# MiniDMXSlave.net
KiCad netlist of a schematic drawn in EAGLE
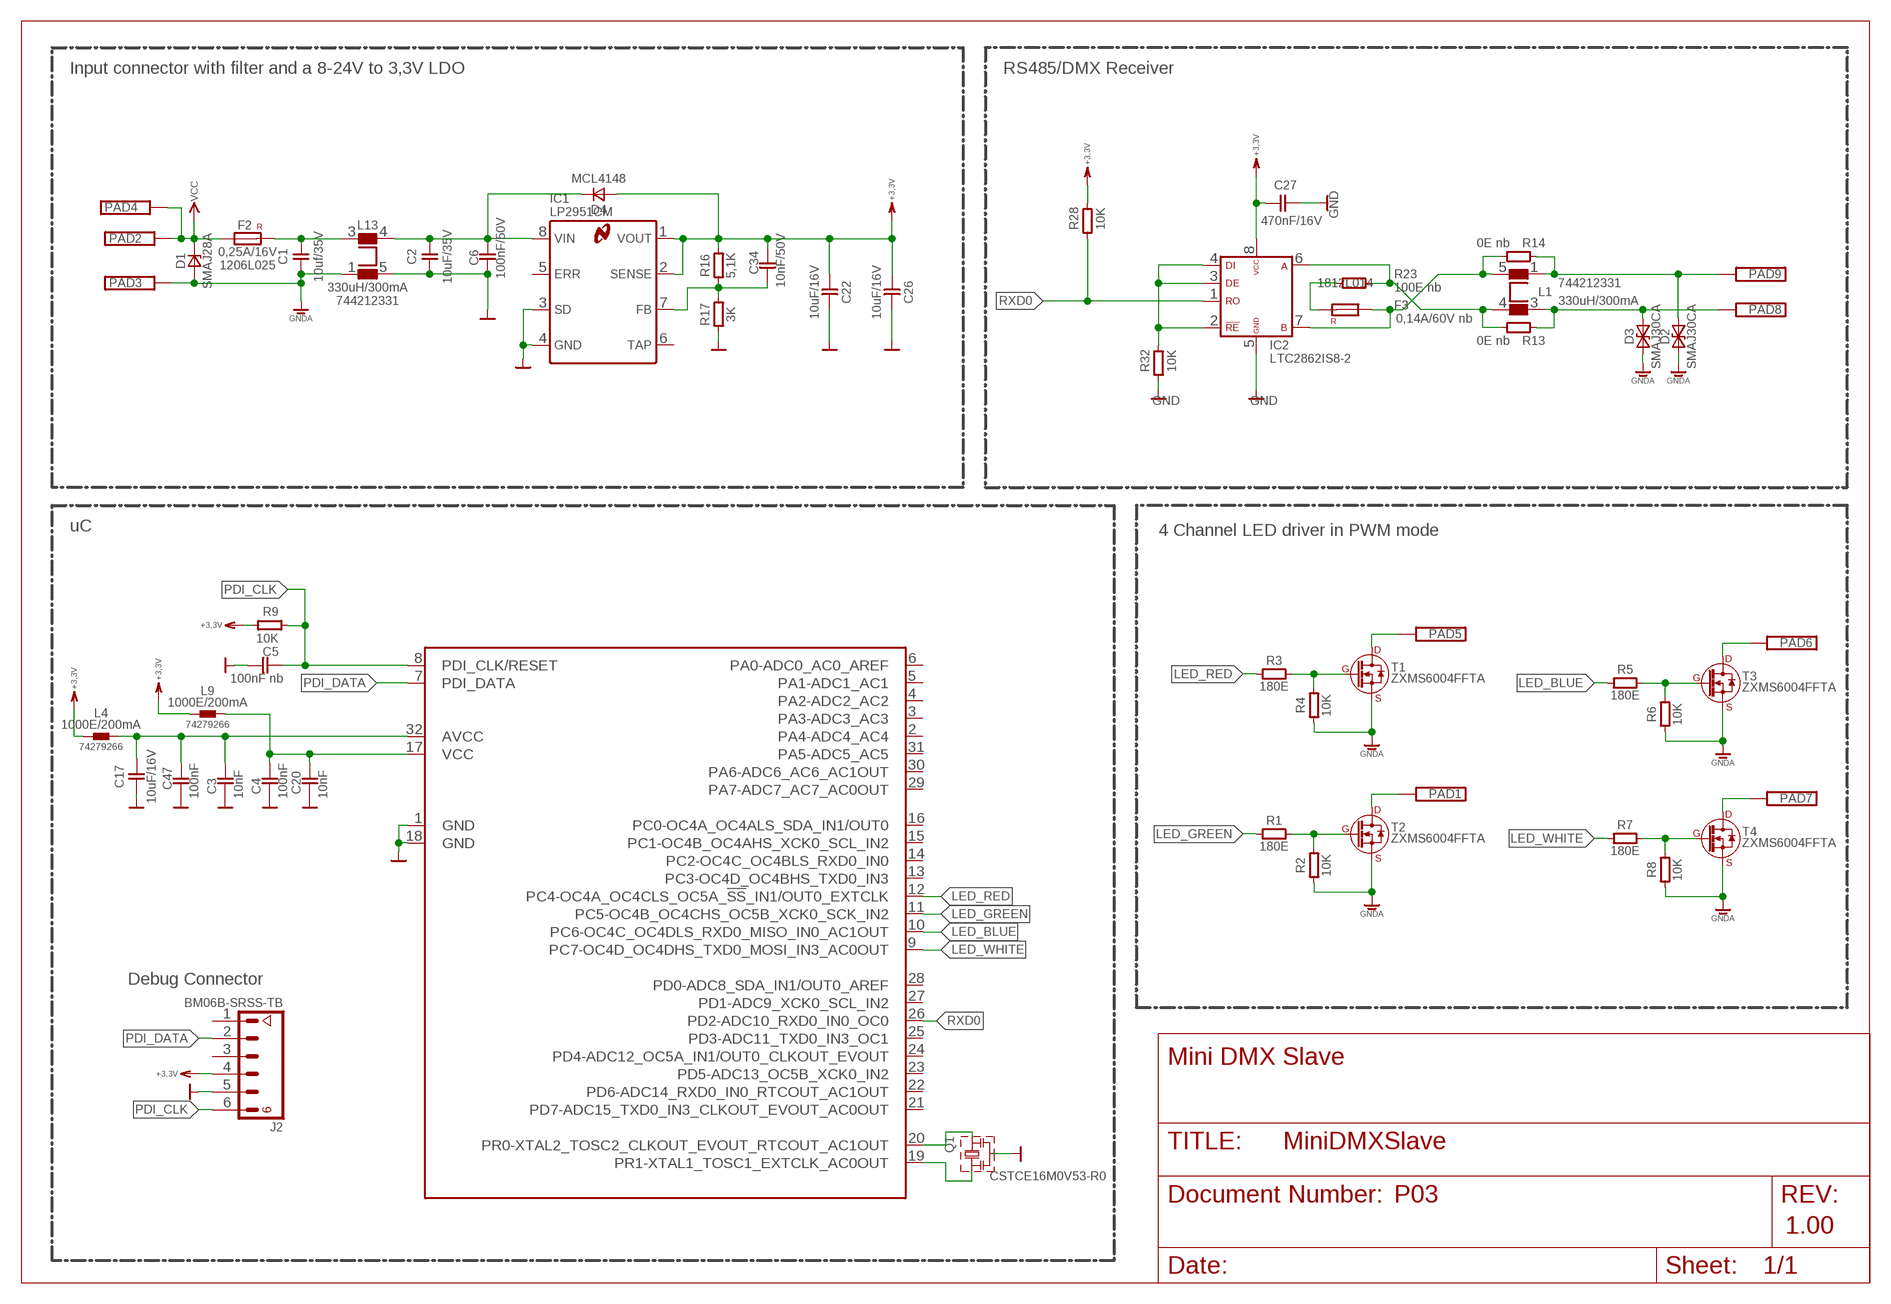
[diagram p0: schematic, sheet 1]

(export (version "E")
  (design (tool "Eeschema 10.0.6"))
  (components
    (comp (ref "C1")
      (value "10uf/35V")
      (footprint "eagle-import:1206")
      (libsource (lib "eagle-import") (part "C-1206"))
    )
    (comp (ref "C2")
      (value "10uF/35V")
      (footprint "eagle-import:1206")
      (libsource (lib "eagle-import") (part "C-1206"))
    )
    (comp (ref "C3")
      (value "10nF")
      (footprint "eagle-import:0603")
      (libsource (lib "eagle-import") (part "C-0603"))
    )
    (comp (ref "C4")
      (value "100nF")
      (footprint "eagle-import:0603")
      (libsource (lib "eagle-import") (part "C-0603"))
    )
    (comp (ref "C5")
      (value "100nF nb")
      (footprint "eagle-import:0603")
      (libsource (lib "eagle-import") (part "C-0603"))
    )
    (comp (ref "C6")
      (value "100nF/50V")
      (footprint "eagle-import:0603")
      (libsource (lib "eagle-import") (part "C-0603"))
    )
    (comp (ref "C17")
      (value "10uF/16V")
      (footprint "eagle-import:0805")
      (libsource (lib "eagle-import") (part "C-0805"))
    )
    (comp (ref "C20")
      (value "10nF")
      (footprint "eagle-import:0603")
      (libsource (lib "eagle-import") (part "C-0603"))
    )
    (comp (ref "C22")
      (value "10uF/16V")
      (footprint "eagle-import:0805")
      (libsource (lib "eagle-import") (part "C-0805"))
    )
    (comp (ref "C26")
      (value "10uF/16V")
      (footprint "eagle-import:0805")
      (libsource (lib "eagle-import") (part "C-0805"))
    )
    (comp (ref "C27")
      (value "470nF/16V")
      (footprint "eagle-import:0603")
      (libsource (lib "eagle-import") (part "C-0603"))
    )
    (comp (ref "C34")
      (value "10nF/50V")
      (footprint "eagle-import:0603")
      (libsource (lib "eagle-import") (part "C-0603"))
    )
    (comp (ref "C47")
      (value "100nF")
      (footprint "eagle-import:0603")
      (libsource (lib "eagle-import") (part "C-0603"))
    )
    (comp (ref "D1")
      (value "SMAJ28A")
      (footprint "eagle-import:DO-214AC")
      (libsource (lib "eagle-import") (part "SMAJA28"))
    )
    (comp (ref "D2")
      (value "SMAJ30CA")
      (footprint "eagle-import:DO-214AC")
      (libsource (lib "eagle-import") (part "SMAJCA30"))
    )
    (comp (ref "D3")
      (value "SMAJ30CA")
      (footprint "eagle-import:DO-214AC")
      (libsource (lib "eagle-import") (part "SMAJCA30"))
    )
    (comp (ref "D4")
      (value "MCL4148")
      (footprint "eagle-import:MICROMELF")
      (libsource (lib "eagle-import") (part "?4148MCL"))
    )
    (comp (ref "F2")
      (value "0,25A/16V")
      (footprint "eagle-import:1206L")
      (fields (field (name "MPN") "1206L025"))
      (libsource (lib "eagle-import") (part "1206L025"))
    )
    (comp (ref "F3")
      (value "0,14A/60V nb")
      (footprint "eagle-import:1812L")
      (fields (field (name "MPN") "1812L014"))
      (libsource (lib "eagle-import") (part "1812L014"))
    )
    (comp (ref "IC1")
      (value "LP2951CM")
      (footprint "eagle-import:SO8")
      (libsource (lib "eagle-import") (part "LP2951CM"))
    )
    (comp (ref "IC2")
      (value "LTC2862IS8-2")
      (footprint "eagle-import:SO8")
      (fields (field (name "MPN") "LTC2862IS8-2#TRPBF"))
      (libsource (lib "eagle-import") (part "LTC2862?-2S8I"))
    )
    (comp (ref "IC3")
      (value "E5-TQFP")
      (footprint "eagle-import:TQFP32")
      (libsource (lib "eagle-import") (part "E5-TQFP"))
    )
    (comp (ref "J2")
      (value "BM06B-SRSS-TB")
      (footprint "eagle-import:BM06B-SRSS-TB")
      (libsource (lib "eagle-import") (part "?M06B-SRSS-TBB"))
    )
    (comp (ref "L1")
      (value "330uH/300mA")
      (footprint "eagle-import:WE-SL1")
      (fields (field (name "MPN") "744212331"))
      (libsource (lib "eagle-import") (part "WE-SL1-330UH/300MA"))
    )
    (comp (ref "L4")
      (value "1000E/200mA")
      (footprint "eagle-import:0603")
      (fields (field (name "MPN") "74279266"))
      (libsource (lib "eagle-import") (part "WE-CBF-0603-1000E/200MA"))
    )
    (comp (ref "L9")
      (value "1000E/200mA")
      (footprint "eagle-import:0603")
      (fields (field (name "MPN") "74279266"))
      (libsource (lib "eagle-import") (part "WE-CBF-0603-1000E/200MA"))
    )
    (comp (ref "L13")
      (value "330uH/300mA")
      (footprint "eagle-import:WE-SL1")
      (fields (field (name "MPN") "744212331"))
      (libsource (lib "eagle-import") (part "WE-SL1-330UH/300MA"))
    )
    (comp (ref "PAD1")
      (value "PADS-6X3")
      (footprint "eagle-import:PAD_6MMX3MM")
      (libsource (lib "eagle-import") (part "PADS-6X3"))
    )
    (comp (ref "PAD2")
      (value "PADS-6X3")
      (footprint "eagle-import:PAD_6MMX3MM")
      (libsource (lib "eagle-import") (part "PADS-6X3"))
    )
    (comp (ref "PAD3")
      (value "PADS-6X3")
      (footprint "eagle-import:PAD_6MMX3MM")
      (libsource (lib "eagle-import") (part "PADS-6X3"))
    )
    (comp (ref "PAD4")
      (value "PADS-6X3")
      (footprint "eagle-import:PAD_6MMX3MM")
      (libsource (lib "eagle-import") (part "PADS-6X3"))
    )
    (comp (ref "PAD5")
      (value "PADS-6X3")
      (footprint "eagle-import:PAD_6MMX3MM")
      (libsource (lib "eagle-import") (part "PADS-6X3"))
    )
    (comp (ref "PAD6")
      (value "PADS-6X3")
      (footprint "eagle-import:PAD_6MMX3MM")
      (libsource (lib "eagle-import") (part "PADS-6X3"))
    )
    (comp (ref "PAD7")
      (value "PADS-6X3")
      (footprint "eagle-import:PAD_6MMX3MM")
      (libsource (lib "eagle-import") (part "PADS-6X3"))
    )
    (comp (ref "PAD8")
      (value "PADS-6X3")
      (footprint "eagle-import:PAD_6MMX3MM")
      (libsource (lib "eagle-import") (part "PADS-6X3"))
    )
    (comp (ref "PAD9")
      (value "PADS-6X3")
      (footprint "eagle-import:PAD_6MMX3MM")
      (libsource (lib "eagle-import") (part "PADS-6X3"))
    )
    (comp (ref "Q1")
      (value "CSTCE16M0V53-R0")
      (footprint "eagle-import:CSTCE_G_&_V")
      (libsource (lib "eagle-import") (part "CSTC?E_G_&_V"))
    )
    (comp (ref "R1")
      (value "180E")
      (footprint "eagle-import:0603")
      (libsource (lib "eagle-import") (part "R-0603"))
    )
    (comp (ref "R2")
      (value "10K")
      (footprint "eagle-import:0603")
      (libsource (lib "eagle-import") (part "R-0603"))
    )
    (comp (ref "R3")
      (value "180E")
      (footprint "eagle-import:0603")
      (libsource (lib "eagle-import") (part "R-0603"))
    )
    (comp (ref "R4")
      (value "10K")
      (footprint "eagle-import:0603")
      (libsource (lib "eagle-import") (part "R-0603"))
    )
    (comp (ref "R5")
      (value "180E")
      (footprint "eagle-import:0603")
      (libsource (lib "eagle-import") (part "R-0603"))
    )
    (comp (ref "R6")
      (value "10K")
      (footprint "eagle-import:0603")
      (libsource (lib "eagle-import") (part "R-0603"))
    )
    (comp (ref "R7")
      (value "180E")
      (footprint "eagle-import:0603")
      (libsource (lib "eagle-import") (part "R-0603"))
    )
    (comp (ref "R8")
      (value "10K")
      (footprint "eagle-import:0603")
      (libsource (lib "eagle-import") (part "R-0603"))
    )
    (comp (ref "R9")
      (value "10K")
      (footprint "eagle-import:0603")
      (libsource (lib "eagle-import") (part "R-0603"))
    )
    (comp (ref "R13")
      (value "0E nb")
      (footprint "eagle-import:0805")
      (libsource (lib "eagle-import") (part "R-0805"))
    )
    (comp (ref "R14")
      (value "0E nb")
      (footprint "eagle-import:0805")
      (libsource (lib "eagle-import") (part "R-0805"))
    )
    (comp (ref "R16")
      (value "5,1K")
      (footprint "eagle-import:0603")
      (libsource (lib "eagle-import") (part "R-0603"))
    )
    (comp (ref "R17")
      (value "3K")
      (footprint "eagle-import:0603")
      (libsource (lib "eagle-import") (part "R-0603"))
    )
    (comp (ref "R23")
      (value "100E nb")
      (footprint "eagle-import:0207")
      (libsource (lib "eagle-import") (part "R-0207"))
    )
    (comp (ref "R28")
      (value "10K")
      (footprint "eagle-import:0603")
      (libsource (lib "eagle-import") (part "R-0603"))
    )
    (comp (ref "R32")
      (value "10K")
      (footprint "eagle-import:0603")
      (libsource (lib "eagle-import") (part "R-0603"))
    )
    (comp (ref "T1")
      (value "ZXMS6004FFTA")
      (footprint "eagle-import:SOT-23")
      (libsource (lib "eagle-import") (part "ZXMS6004?TAFF"))
    )
    (comp (ref "T2")
      (value "ZXMS6004FFTA")
      (footprint "eagle-import:SOT-23")
      (libsource (lib "eagle-import") (part "ZXMS6004?TAFF"))
    )
    (comp (ref "T3")
      (value "ZXMS6004FFTA")
      (footprint "eagle-import:SOT-23")
      (libsource (lib "eagle-import") (part "ZXMS6004?TAFF"))
    )
    (comp (ref "T4")
      (value "ZXMS6004FFTA")
      (footprint "eagle-import:SOT-23")
      (libsource (lib "eagle-import") (part "ZXMS6004?TAFF"))
    )
  )
  (nets
    (net (code "1") (name "+3,3V") (class "Default")
      (node (ref "C22") (pin "1") (pinfunction "1_1") (pintype "passive"))
      (node (ref "C26") (pin "1") (pinfunction "1_1") (pintype "passive"))
      (node (ref "C27") (pin "2") (pinfunction "2_2") (pintype "passive"))
      (node (ref "C34") (pin "2") (pinfunction "2_2") (pintype "passive"))
      (node (ref "D4") (pin "A") (pinfunction "A_A") (pintype "passive"))
      (node (ref "IC1") (pin "1") (pinfunction "VOUT_1") (pintype "power_in"))
      (node (ref "IC1") (pin "2") (pinfunction "SENSE_2") (pintype "bidirectional"))
      (node (ref "IC2") (pin "8") (pinfunction "VCC_8") (pintype "power_in"))
      (node (ref "J2") (pin "4") (pinfunction "4_4") (pintype "passive"))
      (node (ref "L4") (pin "1") (pinfunction "1_1") (pintype "passive"))
      (node (ref "L9") (pin "1") (pinfunction "1_1") (pintype "passive"))
      (node (ref "R16") (pin "2") (pinfunction "2_2") (pintype "passive"))
      (node (ref "R28") (pin "2") (pinfunction "2_2") (pintype "passive"))
      (node (ref "R9") (pin "2") (pinfunction "2_2") (pintype "passive"))
    )
    (net (code "2") (name "GND") (class "Default")
      (node (ref "C17") (pin "1") (pinfunction "1_1") (pintype "passive"))
      (node (ref "C2") (pin "1") (pinfunction "1_1") (pintype "passive"))
      (node (ref "C20") (pin "1") (pinfunction "1_1") (pintype "passive"))
      (node (ref "C22") (pin "2") (pinfunction "2_2") (pintype "passive"))
      (node (ref "C26") (pin "2") (pinfunction "2_2") (pintype "passive"))
      (node (ref "C27") (pin "1") (pinfunction "1_1") (pintype "passive"))
      (node (ref "C3") (pin "1") (pinfunction "1_1") (pintype "passive"))
      (node (ref "C4") (pin "1") (pinfunction "1_1") (pintype "passive"))
      (node (ref "C47") (pin "1") (pinfunction "1_1") (pintype "passive"))
      (node (ref "C5") (pin "2") (pinfunction "2_2") (pintype "passive"))
      (node (ref "C6") (pin "1") (pinfunction "1_1") (pintype "passive"))
      (node (ref "IC1") (pin "3") (pinfunction "SD_3") (pintype "bidirectional"))
      (node (ref "IC1") (pin "4") (pinfunction "GND_4") (pintype "power_in"))
      (node (ref "IC2") (pin "5") (pinfunction "GND_5") (pintype "power_in"))
      (node (ref "IC3") (pin "1") (pinfunction "GND_1") (pintype "power_in"))
      (node (ref "IC3") (pin "18") (pinfunction "GND_18") (pintype "power_in"))
      (node (ref "J2") (pin "5") (pinfunction "5_5") (pintype "passive"))
      (node (ref "L13") (pin "5") (pinfunction "2_5") (pintype "passive"))
      (node (ref "Q1") (pin "2") (pinfunction "GND_2") (pintype "power_in"))
      (node (ref "R17") (pin "1") (pinfunction "1_1") (pintype "passive"))
      (node (ref "R32") (pin "1") (pinfunction "1_1") (pintype "passive"))
    )
    (net (code "3") (name "GNDA") (class "Default")
      (node (ref "C1") (pin "1") (pinfunction "1_1") (pintype "passive"))
      (node (ref "D1") (pin "A") (pinfunction "A_A") (pintype "passive"))
      (node (ref "D2") (pin "K") (pinfunction "2_K") (pintype "passive"))
      (node (ref "D3") (pin "K") (pinfunction "2_K") (pintype "passive"))
      (node (ref "L13") (pin "1") (pinfunction "1_1") (pintype "passive"))
      (node (ref "PAD3") (pin "1") (pinfunction "1_1") (pintype "bidirectional"))
      (node (ref "R2") (pin "1") (pinfunction "1_1") (pintype "passive"))
      (node (ref "R4") (pin "1") (pinfunction "1_1") (pintype "passive"))
      (node (ref "R6") (pin "1") (pinfunction "1_1") (pintype "passive"))
      (node (ref "R8") (pin "1") (pinfunction "1_1") (pintype "passive"))
      (node (ref "T1") (pin "2") (pinfunction "S_2") (pintype "passive"))
      (node (ref "T2") (pin "2") (pinfunction "S_2") (pintype "passive"))
      (node (ref "T3") (pin "2") (pinfunction "S_2") (pintype "passive"))
      (node (ref "T4") (pin "2") (pinfunction "S_2") (pintype "passive"))
    )
    (net (code "4") (name "LED_BLUE") (class "Default")
      (node (ref "IC3") (pin "10") (pinfunction "PC6-OC4C_OC4DLS_RXD0_MISO_IN0_AC1OUT_10") (pintype "bidirectional"))
      (node (ref "R5") (pin "1") (pinfunction "1_1") (pintype "passive"))
    )
    (net (code "5") (name "LED_GREEN") (class "Default")
      (node (ref "IC3") (pin "11") (pinfunction "PC5-OC4B_OC4CHS_OC5B_XCK0_SCK_IN2_11") (pintype "bidirectional"))
      (node (ref "R1") (pin "1") (pinfunction "1_1") (pintype "passive"))
    )
    (net (code "6") (name "LED_RED") (class "Default")
      (node (ref "IC3") (pin "12") (pinfunction "PC4-OC4A_OC4CLS_OC5A_~{SS}_IN1/OUT0_EXTCLK_12") (pintype "bidirectional"))
      (node (ref "R3") (pin "1") (pinfunction "1_1") (pintype "passive"))
    )
    (net (code "7") (name "LED_WHITE") (class "Default")
      (node (ref "IC3") (pin "9") (pinfunction "PC7-OC4D_OC4DHS_TXD0_MOSI_IN3_AC0OUT_9") (pintype "bidirectional"))
      (node (ref "R7") (pin "1") (pinfunction "1_1") (pintype "passive"))
    )
    (net (code "8") (name "Net-(D2-1)") (class "Default")
      (node (ref "D2") (pin "A") (pinfunction "1_A") (pintype "passive"))
      (node (ref "L1") (pin "1") (pinfunction "1_1") (pintype "passive"))
      (node (ref "PAD9") (pin "1") (pinfunction "1_1") (pintype "bidirectional"))
      (node (ref "R14") (pin "1") (pinfunction "1_1") (pintype "passive"))
    )
    (net (code "9") (name "Net-(D3-1)") (class "Default")
      (node (ref "D3") (pin "A") (pinfunction "1_A") (pintype "passive"))
      (node (ref "L1") (pin "3") (pinfunction "4_3") (pintype "passive"))
      (node (ref "PAD8") (pin "1") (pinfunction "1_1") (pintype "bidirectional"))
      (node (ref "R13") (pin "1") (pinfunction "1_1") (pintype "passive"))
    )
    (net (code "10") (name "Net-(F3-Pad2)") (class "Default")
      (node (ref "F3") (pin "2") (pinfunction "2_2") (pintype "passive"))
      (node (ref "R23") (pin "1") (pinfunction "1_1") (pintype "passive"))
    )
    (net (code "11") (name "Net-(IC1-FB)") (class "Default")
      (node (ref "C34") (pin "1") (pinfunction "1_1") (pintype "passive"))
      (node (ref "IC1") (pin "7") (pinfunction "FB_7") (pintype "bidirectional"))
      (node (ref "R16") (pin "1") (pinfunction "1_1") (pintype "passive"))
      (node (ref "R17") (pin "2") (pinfunction "2_2") (pintype "passive"))
    )
    (net (code "12") (name "Net-(IC1-VIN)") (class "Default")
      (node (ref "C2") (pin "2") (pinfunction "2_2") (pintype "passive"))
      (node (ref "C6") (pin "2") (pinfunction "2_2") (pintype "passive"))
      (node (ref "D4") (pin "K") (pinfunction "K_K") (pintype "passive"))
      (node (ref "IC1") (pin "8") (pinfunction "VIN_8") (pintype "power_in"))
      (node (ref "L13") (pin "4") (pinfunction "3_4") (pintype "passive"))
    )
    (net (code "13") (name "Net-(IC2-A)") (class "Default")
      (node (ref "IC2") (pin "6") (pinfunction "A_6") (pintype "bidirectional"))
      (node (ref "L1") (pin "4") (pinfunction "3_4") (pintype "passive"))
      (node (ref "R13") (pin "2") (pinfunction "2_2") (pintype "passive"))
      (node (ref "R23") (pin "2") (pinfunction "2_2") (pintype "passive"))
    )
    (net (code "14") (name "Net-(IC2-B)") (class "Default")
      (node (ref "F3") (pin "1") (pinfunction "1_1") (pintype "passive"))
      (node (ref "IC2") (pin "7") (pinfunction "B_7") (pintype "bidirectional"))
      (node (ref "L1") (pin "5") (pinfunction "2_5") (pintype "passive"))
      (node (ref "R14") (pin "2") (pinfunction "2_2") (pintype "passive"))
    )
    (net (code "15") (name "Net-(IC2-DE)") (class "Default")
      (node (ref "IC2") (pin "2") (pinfunction "/RE_2") (pintype "bidirectional"))
      (node (ref "IC2") (pin "3") (pinfunction "DE_3") (pintype "bidirectional"))
      (node (ref "IC2") (pin "4") (pinfunction "DI_4") (pintype "input"))
      (node (ref "R32") (pin "2") (pinfunction "2_2") (pintype "passive"))
    )
    (net (code "16") (name "Net-(IC3-AVCC)") (class "Default")
      (node (ref "C17") (pin "2") (pinfunction "2_2") (pintype "passive"))
      (node (ref "C3") (pin "2") (pinfunction "2_2") (pintype "passive"))
      (node (ref "C47") (pin "2") (pinfunction "2_2") (pintype "passive"))
      (node (ref "IC3") (pin "32") (pinfunction "AVCC_32") (pintype "power_in"))
      (node (ref "L4") (pin "2") (pinfunction "2_2") (pintype "passive"))
    )
    (net (code "17") (name "Net-(IC3-PR0-XTAL2_TOSC2_CLKOUT_EVOUT_RTCOUT_AC1OUT)") (class "Default")
      (node (ref "IC3") (pin "20") (pinfunction "PR0-XTAL2_TOSC2_CLKOUT_EVOUT_RTCOUT_AC1OUT_20") (pintype "bidirectional"))
      (node (ref "Q1") (pin "3") (pinfunction "OSC2_3") (pintype "passive"))
    )
    (net (code "18") (name "Net-(IC3-PR1-XTAL1_TOSC1_EXTCLK_AC0OUT)") (class "Default")
      (node (ref "IC3") (pin "19") (pinfunction "PR1-XTAL1_TOSC1_EXTCLK_AC0OUT_19") (pintype "bidirectional"))
      (node (ref "Q1") (pin "1") (pinfunction "OSC1_1") (pintype "passive"))
    )
    (net (code "19") (name "Net-(IC3-VCC)") (class "Default")
      (node (ref "C20") (pin "2") (pinfunction "2_2") (pintype "passive"))
      (node (ref "C4") (pin "2") (pinfunction "2_2") (pintype "passive"))
      (node (ref "IC3") (pin "17") (pinfunction "VCC_17") (pintype "power_in"))
      (node (ref "L9") (pin "2") (pinfunction "2_2") (pintype "passive"))
    )
    (net (code "20") (name "Net-(L13-4)") (class "Default")
      (node (ref "C1") (pin "2") (pinfunction "2_2") (pintype "passive"))
      (node (ref "F2") (pin "2") (pinfunction "2_2") (pintype "passive"))
      (node (ref "L13") (pin "3") (pinfunction "4_3") (pintype "passive"))
    )
    (net (code "21") (name "Net-(T1-D)") (class "Default")
      (node (ref "PAD5") (pin "1") (pinfunction "1_1") (pintype "bidirectional"))
      (node (ref "T1") (pin "3") (pinfunction "D_3") (pintype "passive"))
    )
    (net (code "22") (name "Net-(T1-G)") (class "Default")
      (node (ref "R3") (pin "2") (pinfunction "2_2") (pintype "passive"))
      (node (ref "R4") (pin "2") (pinfunction "2_2") (pintype "passive"))
      (node (ref "T1") (pin "1") (pinfunction "G_1") (pintype "passive"))
    )
    (net (code "23") (name "Net-(T2-D)") (class "Default")
      (node (ref "PAD1") (pin "1") (pinfunction "1_1") (pintype "bidirectional"))
      (node (ref "T2") (pin "3") (pinfunction "D_3") (pintype "passive"))
    )
    (net (code "24") (name "Net-(T2-G)") (class "Default")
      (node (ref "R1") (pin "2") (pinfunction "2_2") (pintype "passive"))
      (node (ref "R2") (pin "2") (pinfunction "2_2") (pintype "passive"))
      (node (ref "T2") (pin "1") (pinfunction "G_1") (pintype "passive"))
    )
    (net (code "25") (name "Net-(T3-D)") (class "Default")
      (node (ref "PAD6") (pin "1") (pinfunction "1_1") (pintype "bidirectional"))
      (node (ref "T3") (pin "3") (pinfunction "D_3") (pintype "passive"))
    )
    (net (code "26") (name "Net-(T3-G)") (class "Default")
      (node (ref "R5") (pin "2") (pinfunction "2_2") (pintype "passive"))
      (node (ref "R6") (pin "2") (pinfunction "2_2") (pintype "passive"))
      (node (ref "T3") (pin "1") (pinfunction "G_1") (pintype "passive"))
    )
    (net (code "27") (name "Net-(T4-D)") (class "Default")
      (node (ref "PAD7") (pin "1") (pinfunction "1_1") (pintype "bidirectional"))
      (node (ref "T4") (pin "3") (pinfunction "D_3") (pintype "passive"))
    )
    (net (code "28") (name "Net-(T4-G)") (class "Default")
      (node (ref "R7") (pin "2") (pinfunction "2_2") (pintype "passive"))
      (node (ref "R8") (pin "2") (pinfunction "2_2") (pintype "passive"))
      (node (ref "T4") (pin "1") (pinfunction "G_1") (pintype "passive"))
    )
    (net (code "29") (name "PDI_CLK") (class "Default")
      (node (ref "C5") (pin "1") (pinfunction "1_1") (pintype "passive"))
      (node (ref "IC3") (pin "8") (pinfunction "PDI_CLK/RESET_8") (pintype "bidirectional"))
      (node (ref "J2") (pin "6") (pinfunction "6_6") (pintype "passive"))
      (node (ref "R9") (pin "1") (pinfunction "1_1") (pintype "passive"))
    )
    (net (code "30") (name "PDI_DATA") (class "Default")
      (node (ref "IC3") (pin "7") (pinfunction "PDI_DATA_7") (pintype "bidirectional"))
      (node (ref "J2") (pin "2") (pinfunction "2_2") (pintype "passive"))
    )
    (net (code "31") (name "RXD0") (class "Default")
      (node (ref "IC2") (pin "1") (pinfunction "R0_1") (pintype "output"))
      (node (ref "IC3") (pin "26") (pinfunction "PD2-ADC10_RXD0_IN0_OC0_26") (pintype "bidirectional"))
      (node (ref "R28") (pin "1") (pinfunction "1_1") (pintype "passive"))
    )
    (net (code "32") (name "VCC") (class "Default")
      (node (ref "D1") (pin "K") (pinfunction "K_K") (pintype "passive"))
      (node (ref "F2") (pin "1") (pinfunction "1_1") (pintype "passive"))
      (node (ref "PAD2") (pin "1") (pinfunction "1_1") (pintype "bidirectional"))
      (node (ref "PAD4") (pin "1") (pinfunction "1_1") (pintype "bidirectional"))
    )
    (net (code "33") (name "unconnected-(IC1-ERR-Pad5)") (class "Default")
      (node (ref "IC1") (pin "5") (pinfunction "ERR_5") (pintype "bidirectional"))
    )
    (net (code "34") (name "unconnected-(IC1-TAP-Pad6)") (class "Default")
      (node (ref "IC1") (pin "6") (pinfunction "TAP_6") (pintype "bidirectional"))
    )
    (net (code "35") (name "unconnected-(IC3-PA0-ADC0_AC0_AREF-Pad6)") (class "Default")
      (node (ref "IC3") (pin "6") (pinfunction "PA0-ADC0_AC0_AREF_6") (pintype "bidirectional"))
    )
    (net (code "36") (name "unconnected-(IC3-PA1-ADC1_AC1-Pad5)") (class "Default")
      (node (ref "IC3") (pin "5") (pinfunction "PA1-ADC1_AC1_5") (pintype "bidirectional"))
    )
    (net (code "37") (name "unconnected-(IC3-PA2-ADC2_AC2-Pad4)") (class "Default")
      (node (ref "IC3") (pin "4") (pinfunction "PA2-ADC2_AC2_4") (pintype "bidirectional"))
    )
    (net (code "38") (name "unconnected-(IC3-PA3-ADC3_AC3-Pad3)") (class "Default")
      (node (ref "IC3") (pin "3") (pinfunction "PA3-ADC3_AC3_3") (pintype "bidirectional"))
    )
    (net (code "39") (name "unconnected-(IC3-PA4-ADC4_AC4-Pad2)") (class "Default")
      (node (ref "IC3") (pin "2") (pinfunction "PA4-ADC4_AC4_2") (pintype "bidirectional"))
    )
    (net (code "40") (name "unconnected-(IC3-PA5-ADC5_AC5-Pad31)") (class "Default")
      (node (ref "IC3") (pin "31") (pinfunction "PA5-ADC5_AC5_31") (pintype "bidirectional"))
    )
    (net (code "41") (name "unconnected-(IC3-PA6-ADC6_AC6_AC1OUT-Pad30)") (class "Default")
      (node (ref "IC3") (pin "30") (pinfunction "PA6-ADC6_AC6_AC1OUT_30") (pintype "bidirectional"))
    )
    (net (code "42") (name "unconnected-(IC3-PA7-ADC7_AC7_AC0OUT-Pad29)") (class "Default")
      (node (ref "IC3") (pin "29") (pinfunction "PA7-ADC7_AC7_AC0OUT_29") (pintype "bidirectional"))
    )
    (net (code "43") (name "unconnected-(IC3-PC0-OC4A_OC4ALS_SDA_IN1{slash}OUT0-Pad16)") (class "Default")
      (node (ref "IC3") (pin "16") (pinfunction "PC0-OC4A_OC4ALS_SDA_IN1/OUT0_16") (pintype "bidirectional"))
    )
    (net (code "44") (name "unconnected-(IC3-PC1-OC4B_OC4AHS_XCK0_SCL_IN2-Pad15)") (class "Default")
      (node (ref "IC3") (pin "15") (pinfunction "PC1-OC4B_OC4AHS_XCK0_SCL_IN2_15") (pintype "bidirectional"))
    )
    (net (code "45") (name "unconnected-(IC3-PC2-OC4C_OC4BLS_RXD0_IN0-Pad14)") (class "Default")
      (node (ref "IC3") (pin "14") (pinfunction "PC2-OC4C_OC4BLS_RXD0_IN0_14") (pintype "bidirectional"))
    )
    (net (code "46") (name "unconnected-(IC3-PC3-OC4D_OC4BHS_TXD0_IN3-Pad13)") (class "Default")
      (node (ref "IC3") (pin "13") (pinfunction "PC3-OC4D_OC4BHS_TXD0_IN3_13") (pintype "bidirectional"))
    )
    (net (code "47") (name "unconnected-(IC3-PD0-ADC8_SDA_IN1{slash}OUT0_AREF-Pad28)") (class "Default")
      (node (ref "IC3") (pin "28") (pinfunction "PD0-ADC8_SDA_IN1/OUT0_AREF_28") (pintype "bidirectional"))
    )
    (net (code "48") (name "unconnected-(IC3-PD1-ADC9_XCK0_SCL_IN2-Pad27)") (class "Default")
      (node (ref "IC3") (pin "27") (pinfunction "PD1-ADC9_XCK0_SCL_IN2_27") (pintype "bidirectional"))
    )
    (net (code "49") (name "unconnected-(IC3-PD3-ADC11_TXD0_IN3_OC1-Pad25)") (class "Default")
      (node (ref "IC3") (pin "25") (pinfunction "PD3-ADC11_TXD0_IN3_OC1_25") (pintype "bidirectional"))
    )
    (net (code "50") (name "unconnected-(IC3-PD4-ADC12_OC5A_IN1{slash}OUT0_CLKOUT_EVOUT-Pad24)") (class "Default")
      (node (ref "IC3") (pin "24") (pinfunction "PD4-ADC12_OC5A_IN1/OUT0_CLKOUT_EVOUT_24") (pintype "bidirectional"))
    )
    (net (code "51") (name "unconnected-(IC3-PD5-ADC13_OC5B_XCK0_IN2-Pad23)") (class "Default")
      (node (ref "IC3") (pin "23") (pinfunction "PD5-ADC13_OC5B_XCK0_IN2_23") (pintype "bidirectional"))
    )
    (net (code "52") (name "unconnected-(IC3-PD6-ADC14_RXD0_IN0_RTCOUT_AC1OUT-Pad22)") (class "Default")
      (node (ref "IC3") (pin "22") (pinfunction "PD6-ADC14_RXD0_IN0_RTCOUT_AC1OUT_22") (pintype "bidirectional"))
    )
    (net (code "53") (name "unconnected-(IC3-PD7-ADC15_TXD0_IN3_CLKOUT_EVOUT_AC0OUT-Pad21)") (class "Default")
      (node (ref "IC3") (pin "21") (pinfunction "PD7-ADC15_TXD0_IN3_CLKOUT_EVOUT_AC0OUT_21") (pintype "bidirectional"))
    )
    (net (code "54") (name "unconnected-(J2-Pad1)") (class "Default")
      (node (ref "J2") (pin "1") (pinfunction "1_1") (pintype "passive"))
    )
    (net (code "55") (name "unconnected-(J2-Pad3)") (class "Default")
      (node (ref "J2") (pin "3") (pinfunction "3_3") (pintype "passive"))
    )
  )
)
